# RS485.net
KiCad netlist of a schematic drawn in Altium Designer
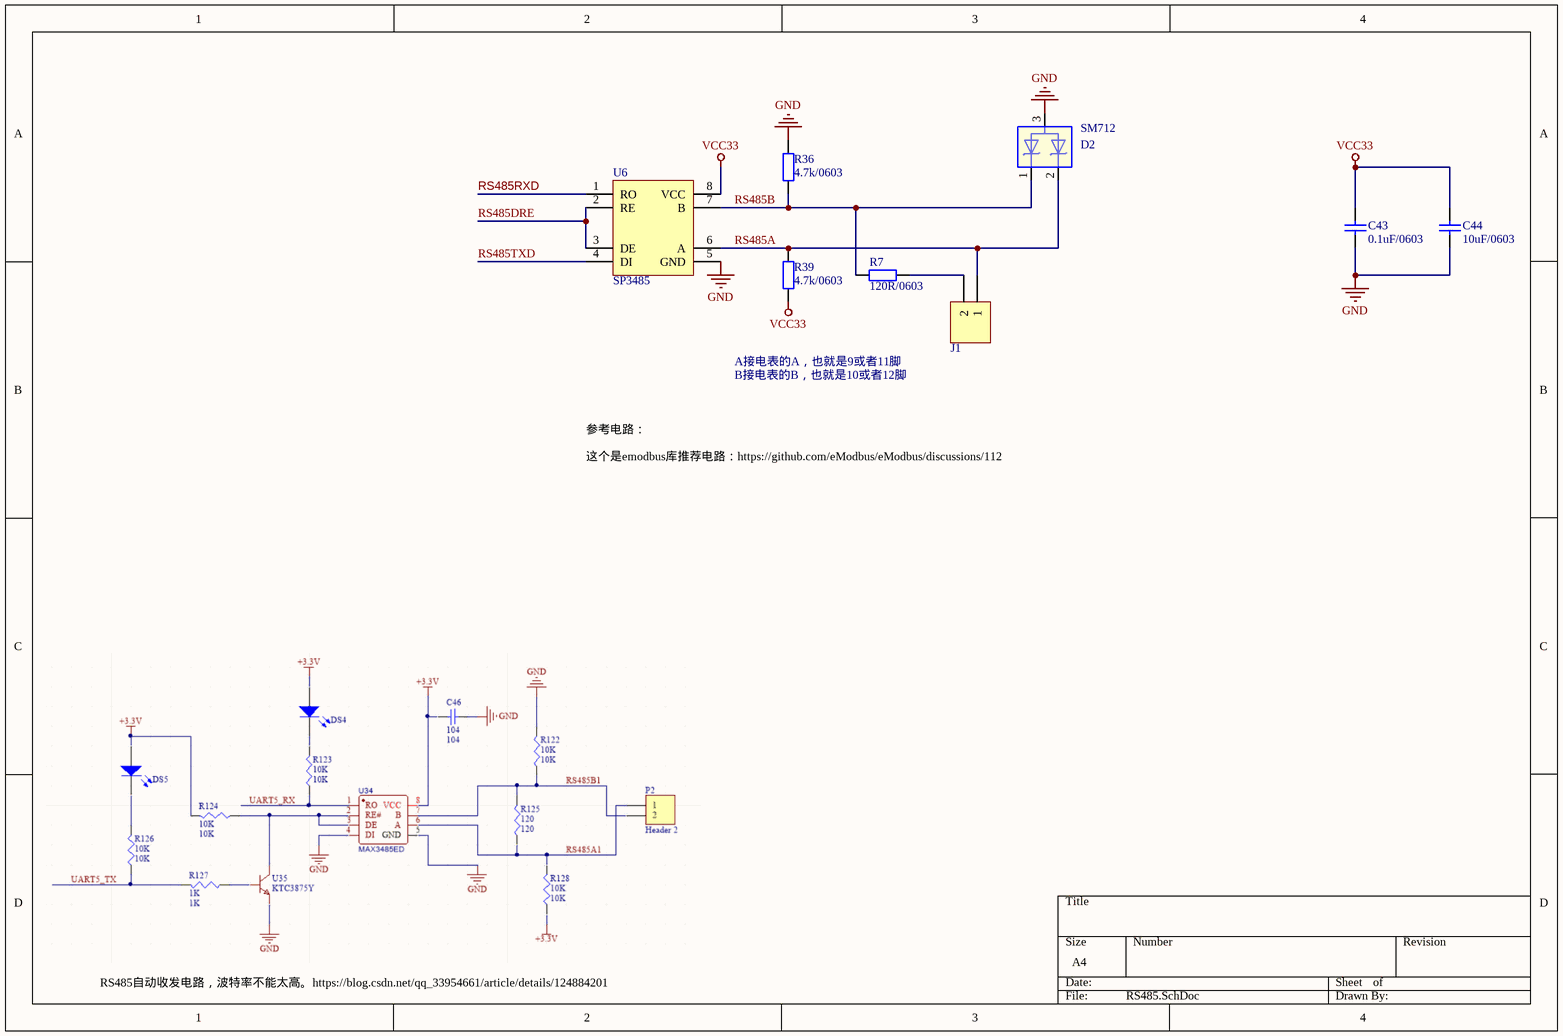
[diagram p0: RS485.SchDoc]

(export (version "E")
  (design (tool "Eeschema 10.0.6"))
  (components
    (comp (ref "C43")
      (value "0.1uF/0603")
      (footprint "CAP0603")
      (description "Capacitor (Semiconductor SIM Model)")
      (fields (field (name "PUBLISHER") "Altium Limited"))
      (libsource (lib "Miscellaneous Devices") (part "Cap Semi"))
    )
    (comp (ref "C44")
      (value "10uF/0603")
      (footprint "CAP0603")
      (description "Capacitor (Semiconductor SIM Model)")
      (fields (field (name "PUBLISHER") "Altium Limited"))
      (libsource (lib "Miscellaneous Devices") (part "Cap Semi"))
    )
    (comp (ref "D2")
      (value "SM712")
      (footprint "SOT95P280X135-3N")
      (description "兩路TVS二极管阵列")
      (fields (field (name "PART NUMBER") "702112964"))
      (libsource (lib "*") (part "SM05_D24"))
    )
    (comp (ref "J1")
      (value "Jumper")
      (footprint "HDR1X2")
      (description "Header, 2-Pin")
      (fields (field (name "PUBLISHER") "Altium Limited"))
      (libsource (lib "Miscellaneous Connectors") (part "Header 2"))
    )
    (comp (ref "R7")
      (value "120R/0603")
      (footprint "RES0603")
      (description "Resistor")
      (fields (field (name "PUBLISHER") "Altium Limited"))
      (libsource (lib "") (part "Res2_1"))
    )
    (comp (ref "R36")
      (value "4.7k/0603")
      (footprint "RES0603")
      (fields (field (name "PUBLISHER") "Altium Limited"))
      (libsource (lib "Miscellaneous Devices") (part "Res2"))
    )
    (comp (ref "R39")
      (value "4.7k/0603")
      (footprint "RES0603")
      (fields (field (name "PUBLISHER") "Altium Limited"))
      (libsource (lib "Miscellaneous Devices") (part "Res2"))
    )
    (comp (ref "U6")
      (value "SP3485")
      (footprint "SP3485-SOP8")
      (description "485总线芯片")
      (libsource (lib "fszhang") (part "SP3485"))
    )
  )
  (nets
    (net (code "1") (name "/RS485A") (class "Default")
      (node (ref "D2") (pin "2") (pinfunction "2_2") (pintype "passive"))
      (node (ref "J1") (pin "1") (pinfunction "1_1") (pintype "passive"))
      (node (ref "R39") (pin "1") (pinfunction "1_1") (pintype "passive"))
      (node (ref "U6") (pin "6") (pinfunction "A_6") (pintype "passive"))
    )
    (net (code "2") (name "/RS485B") (class "Default")
      (node (ref "D2") (pin "1") (pinfunction "1_1") (pintype "passive"))
      (node (ref "R36") (pin "2") (pinfunction "2_2") (pintype "passive"))
      (node (ref "R7") (pin "1") (pinfunction "1_1") (pintype "passive"))
      (node (ref "U6") (pin "7") (pinfunction "B_7") (pintype "passive"))
    )
    (net (code "3") (name "/RS485DRE") (class "Default")
      (node (ref "U6") (pin "2") (pinfunction "RE_2") (pintype "passive"))
      (node (ref "U6") (pin "3") (pinfunction "DE_3") (pintype "passive"))
    )
    (net (code "4") (name "/RS485RXD") (class "Default")
      (node (ref "U6") (pin "1") (pinfunction "RO_1") (pintype "passive"))
    )
    (net (code "5") (name "/RS485TXD") (class "Default")
      (node (ref "U6") (pin "4") (pinfunction "DI_4") (pintype "passive"))
    )
    (net (code "6") (name "GND") (class "Default")
      (node (ref "C43") (pin "1") (pinfunction "1_1") (pintype "passive"))
      (node (ref "C44") (pin "1") (pinfunction "1_1") (pintype "passive"))
      (node (ref "D2") (pin "3") (pinfunction "3_3") (pintype "passive"))
      (node (ref "R36") (pin "1") (pinfunction "1_1") (pintype "passive"))
      (node (ref "U6") (pin "5") (pinfunction "GND_5") (pintype "passive"))
    )
    (net (code "7") (name "Net-(J1-Pad2)") (class "Default")
      (node (ref "J1") (pin "2") (pinfunction "2_2") (pintype "passive"))
      (node (ref "R7") (pin "2") (pinfunction "2_2") (pintype "passive"))
    )
    (net (code "8") (name "VCC33") (class "Default")
      (node (ref "C43") (pin "2") (pinfunction "2_2") (pintype "passive"))
      (node (ref "C44") (pin "2") (pinfunction "2_2") (pintype "passive"))
      (node (ref "R39") (pin "2") (pinfunction "2_2") (pintype "passive"))
      (node (ref "U6") (pin "8") (pinfunction "VCC_8") (pintype "passive"))
    )
  )
)
